# BetaRev1.net
KiCad netlist of a schematic drawn in EAGLE
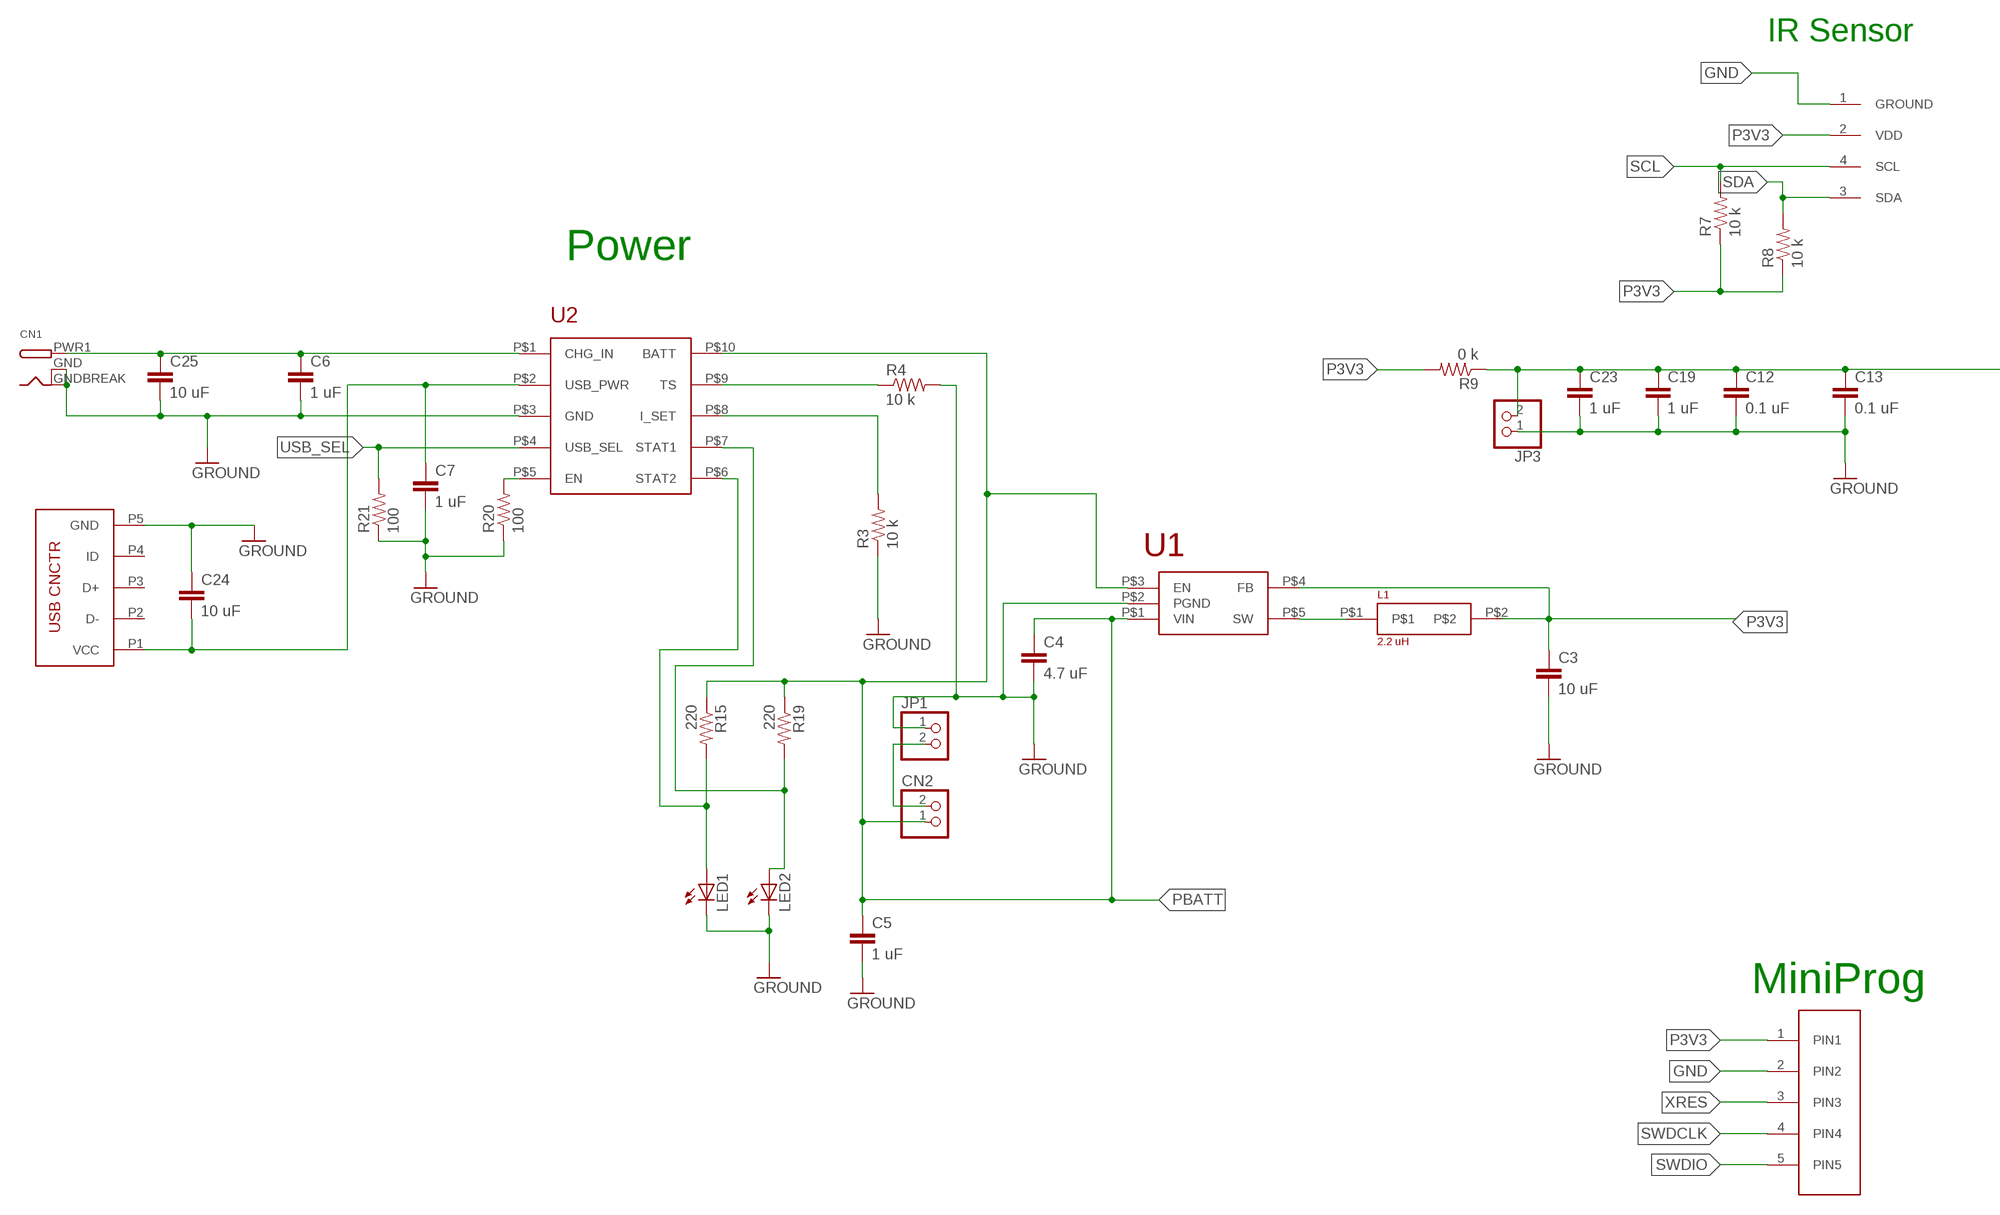
[diagram p0: schematic, sheet 1, part 1 of 2]
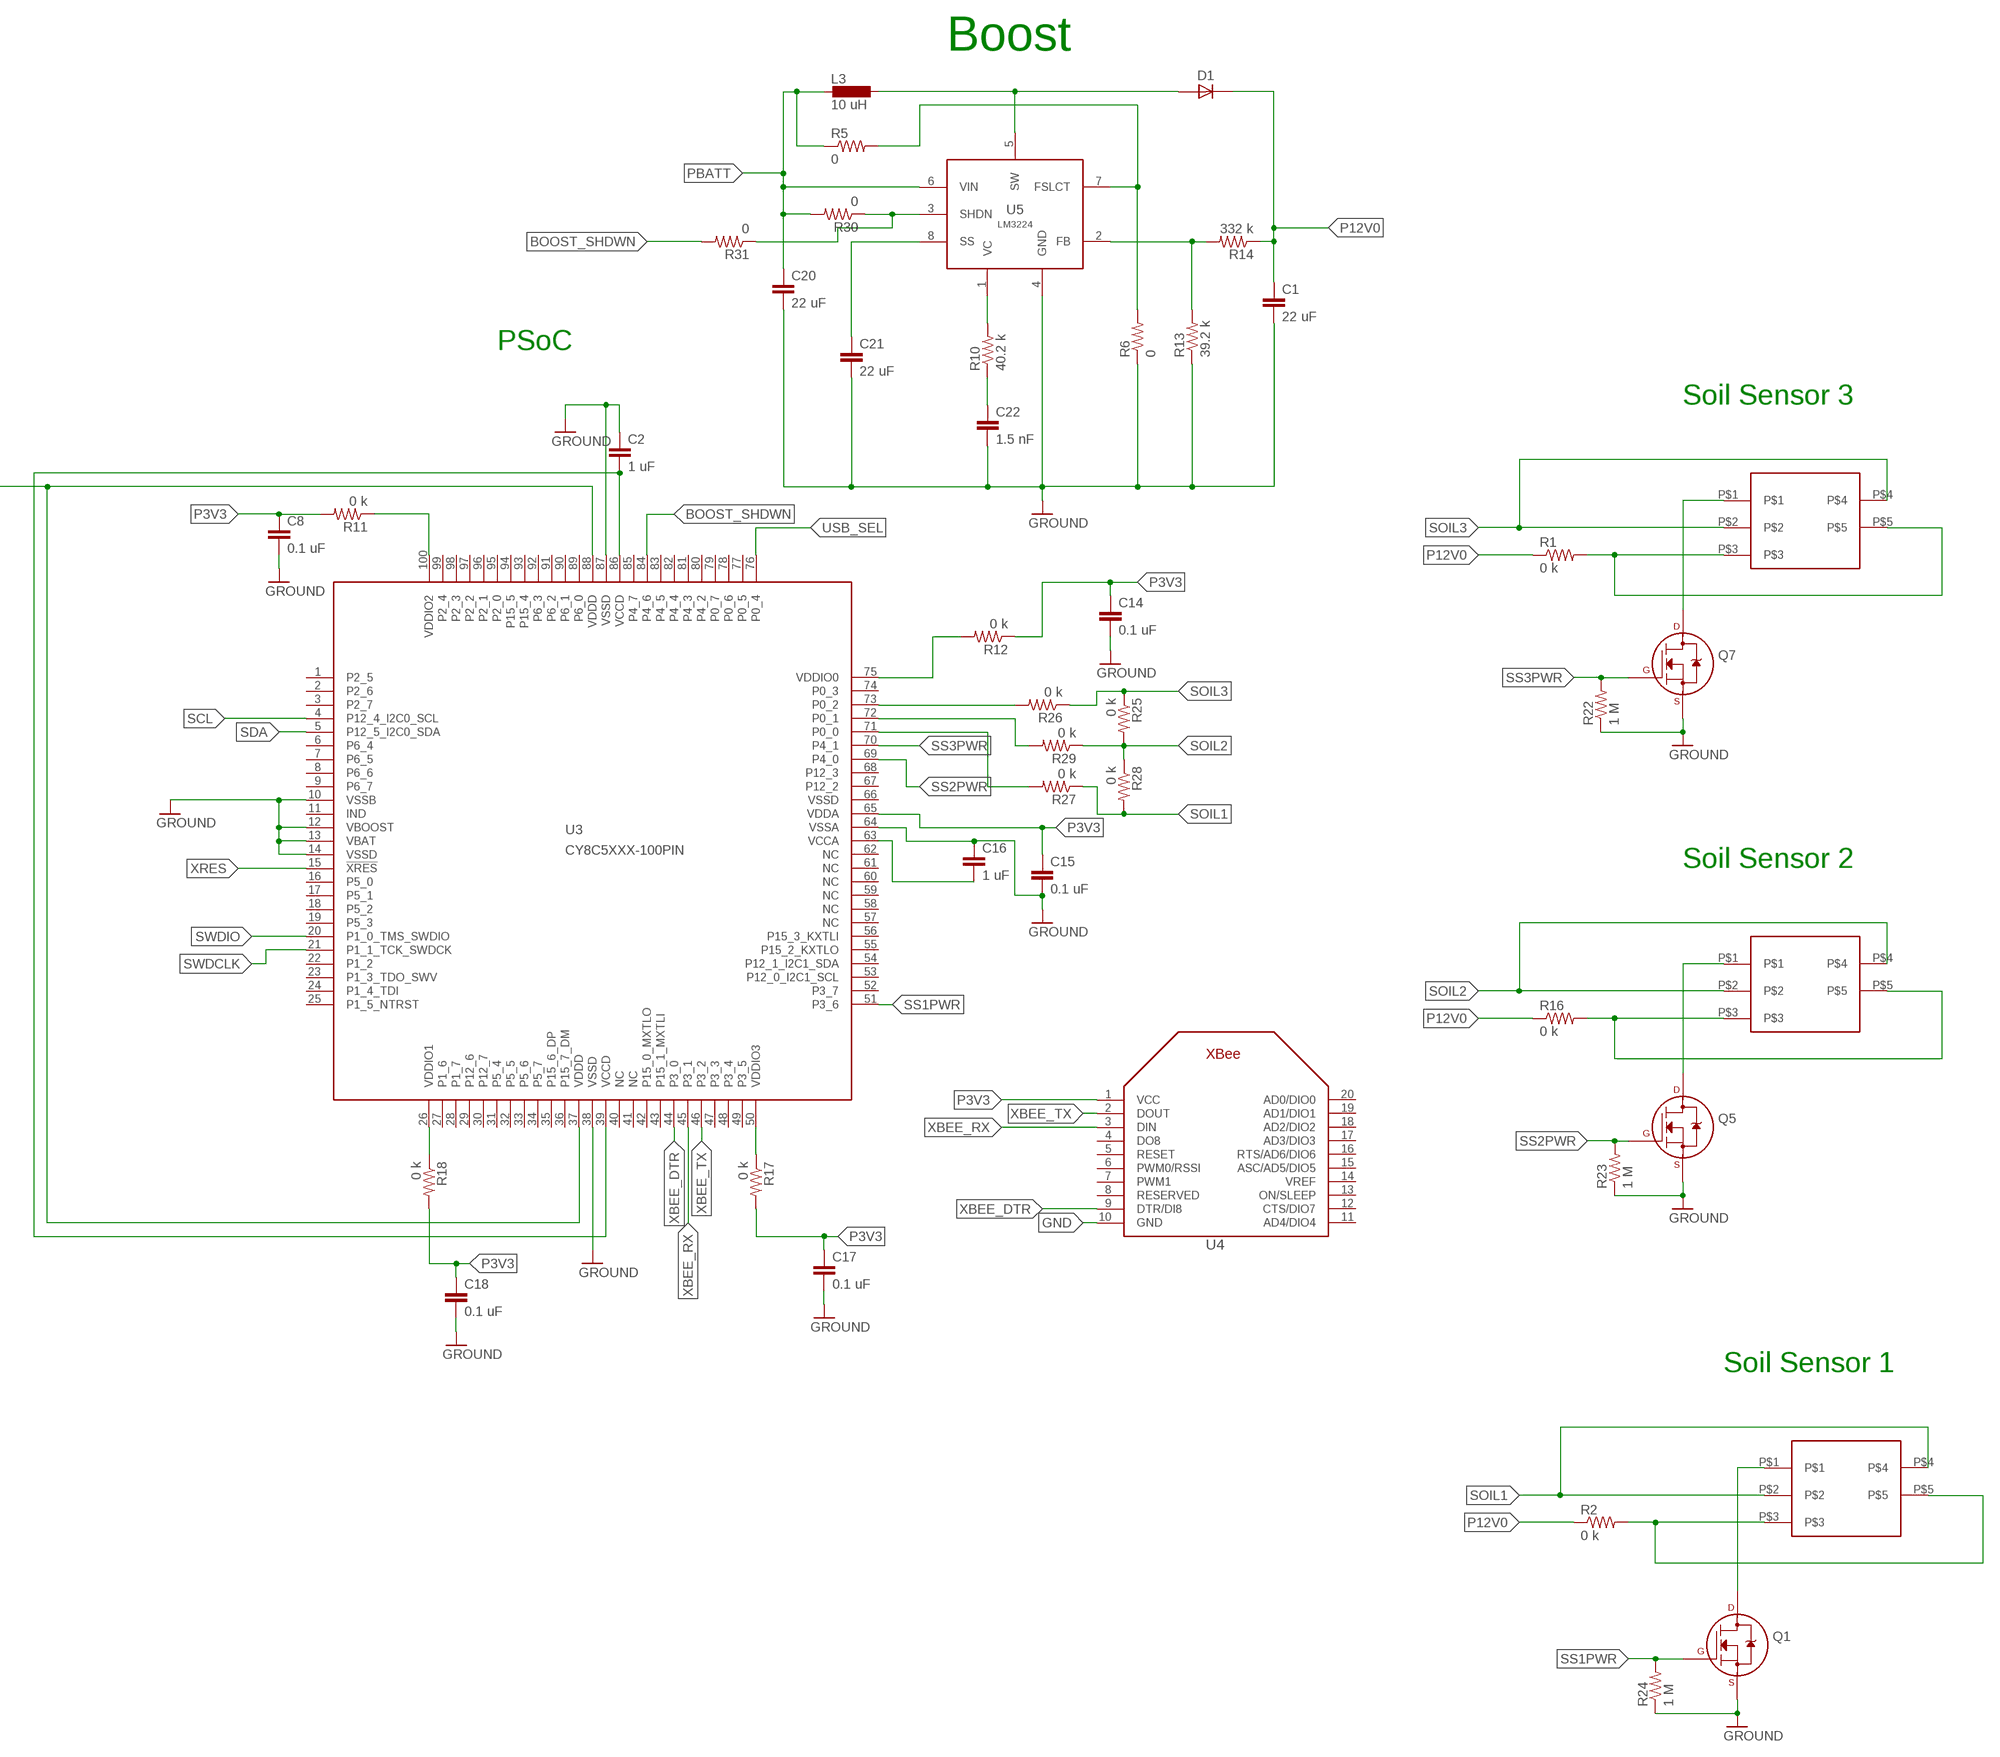
[diagram p1: schematic, sheet 1, part 2 of 2]

(export (version "E")
  (design (tool "Eeschema 10.0.6"))
  (components
    (comp (ref "C1")
      (value "22 uF")
      (footprint "eagle-import:0805")
      (libsource (lib "eagle-import") (part "CAPACITOR0805"))
    )
    (comp (ref "C2")
      (value "1 uF")
      (footprint "eagle-import:0603")
      (libsource (lib "eagle-import") (part "CAPACITOR0603"))
    )
    (comp (ref "C3")
      (value "10 uF")
      (footprint "eagle-import:0603")
      (libsource (lib "eagle-import") (part "CAPACITOR0603"))
    )
    (comp (ref "C4")
      (value "4.7 uF")
      (footprint "eagle-import:0603")
      (libsource (lib "eagle-import") (part "CAPACITOR0603"))
    )
    (comp (ref "C5")
      (value "1 uF")
      (footprint "eagle-import:0603")
      (libsource (lib "eagle-import") (part "CAPACITOR0603"))
    )
    (comp (ref "C6")
      (value "1 uF")
      (footprint "eagle-import:0603")
      (libsource (lib "eagle-import") (part "CAPACITOR0603"))
    )
    (comp (ref "C7")
      (value "1 uF")
      (footprint "eagle-import:0603")
      (libsource (lib "eagle-import") (part "CAPACITOR0603"))
    )
    (comp (ref "C8")
      (value "0.1 uF")
      (footprint "eagle-import:0603")
      (libsource (lib "eagle-import") (part "CAPACITOR0603"))
    )
    (comp (ref "C12")
      (value "0.1 uF")
      (footprint "eagle-import:0603")
      (libsource (lib "eagle-import") (part "CAPACITOR0603"))
    )
    (comp (ref "C13")
      (value "0.1 uF")
      (footprint "eagle-import:0603")
      (libsource (lib "eagle-import") (part "CAPACITOR0603"))
    )
    (comp (ref "C14")
      (value "0.1 uF")
      (footprint "eagle-import:0603")
      (libsource (lib "eagle-import") (part "CAPACITOR0603"))
    )
    (comp (ref "C15")
      (value "0.1 uF")
      (footprint "eagle-import:0603")
      (libsource (lib "eagle-import") (part "CAPACITOR0603"))
    )
    (comp (ref "C16")
      (value "1 uF")
      (footprint "eagle-import:0603")
      (libsource (lib "eagle-import") (part "CAPACITOR0603"))
    )
    (comp (ref "C17")
      (value "0.1 uF")
      (footprint "eagle-import:0603")
      (libsource (lib "eagle-import") (part "CAPACITOR0603"))
    )
    (comp (ref "C18")
      (value "0.1 uF")
      (footprint "eagle-import:0603")
      (libsource (lib "eagle-import") (part "CAPACITOR0603"))
    )
    (comp (ref "C19")
      (value "1 uF")
      (footprint "eagle-import:0603")
      (libsource (lib "eagle-import") (part "CAPACITOR0603"))
    )
    (comp (ref "C20")
      (value "22 uF")
      (footprint "eagle-import:0603")
      (libsource (lib "eagle-import") (part "CAPACITOR0603"))
    )
    (comp (ref "C21")
      (value "22 uF")
      (footprint "eagle-import:0603")
      (libsource (lib "eagle-import") (part "CAPACITOR0603"))
    )
    (comp (ref "C22")
      (value "1.5 nF")
      (footprint "eagle-import:0603")
      (libsource (lib "eagle-import") (part "CAPACITOR0603"))
    )
    (comp (ref "C23")
      (value "1 uF")
      (footprint "eagle-import:0603")
      (libsource (lib "eagle-import") (part "CAPACITOR0603"))
    )
    (comp (ref "C24")
      (value "10 uF")
      (footprint "eagle-import:0603")
      (libsource (lib "eagle-import") (part "CAPACITOR0603"))
    )
    (comp (ref "C25")
      (value "10 uF")
      (footprint "eagle-import:0603")
      (libsource (lib "eagle-import") (part "CAPACITOR0603"))
    )
    (comp (ref "CN1")
      (value "DCBARRELSMT")
      (footprint "eagle-import:DCJACK_2MM_SMT")
      (libsource (lib "eagle-import") (part "DCBARRELSMT"))
    )
    (comp (ref "CN2")
      (value "JST_2PIN-SMT-RA")
      (footprint "eagle-import:JST-PH-2-SMT-RA")
      (libsource (lib "eagle-import") (part "JST_2PIN-SMT-RA"))
    )
    (comp (ref "D1")
      (value "DIODE")
      (footprint "eagle-import:0603-LED")
      (libsource (lib "eagle-import") (part "DIODE"))
    )
    (comp (ref "IRSENSOR")
      (value "TO39")
      (footprint "eagle-import:TO39")
      (libsource (lib "eagle-import") (part "TO39"))
    )
    (comp (ref "JP1")
      (value "PINHD-1X2")
      (footprint "eagle-import:1X02")
      (libsource (lib "eagle-import") (part "PINHD-1X2"))
    )
    (comp (ref "JP3")
      (value "PINHD-1X2")
      (footprint "eagle-import:1X02")
      (libsource (lib "eagle-import") (part "PINHD-1X2"))
    )
    (comp (ref "L1")
      (value "LPO3310")
      (footprint "eagle-import:LPO3310")
      (libsource (lib "eagle-import") (part "LPO3310"))
    )
    (comp (ref "L3")
      (value "10 uH")
      (footprint "eagle-import:DO3316P")
      (libsource (lib "eagle-import") (part "DO3316P"))
    )
    (comp (ref "LED1")
      (value "LEDCHIP-LED0603")
      (footprint "eagle-import:CHIP-LED0603")
      (libsource (lib "eagle-import") (part "LEDCHIP-LED0603"))
    )
    (comp (ref "LED2")
      (value "LEDCHIP-LED0603")
      (footprint "eagle-import:CHIP-LED0603")
      (libsource (lib "eagle-import") (part "LEDCHIP-LED0603"))
    )
    (comp (ref "MINIPROG")
      (value "HEADER-5")
      (footprint "eagle-import:NON-5")
      (libsource (lib "eagle-import") (part "HEADER-5"))
    )
    (comp (ref "Q1")
      (value "2N7000_SOT23")
      (footprint "eagle-import:SOT-23")
      (libsource (lib "eagle-import") (part "2N700_SOT230"))
    )
    (comp (ref "Q5")
      (value "2N7000_SOT23")
      (footprint "eagle-import:SOT-23")
      (libsource (lib "eagle-import") (part "2N700_SOT230"))
    )
    (comp (ref "Q7")
      (value "2N7000_SOT23")
      (footprint "eagle-import:SOT-23")
      (libsource (lib "eagle-import") (part "2N700_SOT230"))
    )
    (comp (ref "R1")
      (value "0 k")
      (footprint "eagle-import:0603")
      (libsource (lib "eagle-import") (part "RESISTOR0603"))
    )
    (comp (ref "R2")
      (value "0 k")
      (footprint "eagle-import:0603")
      (libsource (lib "eagle-import") (part "RESISTOR0603"))
    )
    (comp (ref "R3")
      (value "10 k")
      (footprint "eagle-import:0603")
      (libsource (lib "eagle-import") (part "RESISTOR0603"))
    )
    (comp (ref "R4")
      (value "10 k")
      (footprint "eagle-import:0603")
      (libsource (lib "eagle-import") (part "RESISTOR0603"))
    )
    (comp (ref "R5")
      (value "0")
      (footprint "eagle-import:0603")
      (libsource (lib "eagle-import") (part "RESISTOR0603"))
    )
    (comp (ref "R6")
      (value "0")
      (footprint "eagle-import:0603")
      (libsource (lib "eagle-import") (part "RESISTOR0603"))
    )
    (comp (ref "R7")
      (value "10 k")
      (footprint "eagle-import:0603")
      (libsource (lib "eagle-import") (part "RESISTOR0603"))
    )
    (comp (ref "R8")
      (value "10 k")
      (footprint "eagle-import:0603")
      (libsource (lib "eagle-import") (part "RESISTOR0603"))
    )
    (comp (ref "R9")
      (value "0 k")
      (footprint "eagle-import:0603")
      (libsource (lib "eagle-import") (part "RESISTOR0603"))
    )
    (comp (ref "R10")
      (value "40.2 k")
      (footprint "eagle-import:0603")
      (libsource (lib "eagle-import") (part "RESISTOR0603"))
    )
    (comp (ref "R11")
      (value "0 k")
      (footprint "eagle-import:0603")
      (libsource (lib "eagle-import") (part "RESISTOR0603"))
    )
    (comp (ref "R12")
      (value "0 k")
      (footprint "eagle-import:0603")
      (libsource (lib "eagle-import") (part "RESISTOR0603"))
    )
    (comp (ref "R13")
      (value "39.2 k")
      (footprint "eagle-import:0603")
      (libsource (lib "eagle-import") (part "RESISTOR0603"))
    )
    (comp (ref "R14")
      (value "332 k")
      (footprint "eagle-import:0603")
      (libsource (lib "eagle-import") (part "RESISTOR0603"))
    )
    (comp (ref "R15")
      (value "220")
      (footprint "eagle-import:0603")
      (libsource (lib "eagle-import") (part "RESISTOR0603"))
    )
    (comp (ref "R16")
      (value "0 k")
      (footprint "eagle-import:0603")
      (libsource (lib "eagle-import") (part "RESISTOR0603"))
    )
    (comp (ref "R17")
      (value "0 k")
      (footprint "eagle-import:0603")
      (libsource (lib "eagle-import") (part "RESISTOR0603"))
    )
    (comp (ref "R18")
      (value "0 k")
      (footprint "eagle-import:0603")
      (libsource (lib "eagle-import") (part "RESISTOR0603"))
    )
    (comp (ref "R19")
      (value "220")
      (footprint "eagle-import:0603")
      (libsource (lib "eagle-import") (part "RESISTOR0603"))
    )
    (comp (ref "R20")
      (value "100")
      (footprint "eagle-import:0603")
      (libsource (lib "eagle-import") (part "RESISTOR0603"))
    )
    (comp (ref "R21")
      (value "100")
      (footprint "eagle-import:0603")
      (libsource (lib "eagle-import") (part "RESISTOR0603"))
    )
    (comp (ref "R22")
      (value "1 M")
      (footprint "eagle-import:0603")
      (libsource (lib "eagle-import") (part "RESISTOR0603"))
    )
    (comp (ref "R23")
      (value "1 M")
      (footprint "eagle-import:0603")
      (libsource (lib "eagle-import") (part "RESISTOR0603"))
    )
    (comp (ref "R24")
      (value "1 M")
      (footprint "eagle-import:0603")
      (libsource (lib "eagle-import") (part "RESISTOR0603"))
    )
    (comp (ref "R25")
      (value "0 k")
      (footprint "eagle-import:0603")
      (libsource (lib "eagle-import") (part "RESISTOR0603"))
    )
    (comp (ref "R26")
      (value "0 k")
      (footprint "eagle-import:0603")
      (libsource (lib "eagle-import") (part "RESISTOR0603"))
    )
    (comp (ref "R27")
      (value "0 k")
      (footprint "eagle-import:0603")
      (libsource (lib "eagle-import") (part "RESISTOR0603"))
    )
    (comp (ref "R28")
      (value "0 k")
      (footprint "eagle-import:0603")
      (libsource (lib "eagle-import") (part "RESISTOR0603"))
    )
    (comp (ref "R29")
      (value "0 k")
      (footprint "eagle-import:0603")
      (libsource (lib "eagle-import") (part "RESISTOR0603"))
    )
    (comp (ref "R30")
      (value "0")
      (footprint "eagle-import:0603")
      (libsource (lib "eagle-import") (part "RESISTOR0603"))
    )
    (comp (ref "R31")
      (value "0")
      (footprint "eagle-import:0603")
      (libsource (lib "eagle-import") (part "RESISTOR0603"))
    )
    (comp (ref "U$1")
      (value "FCI10118192-0001LF")
      (footprint "eagle-import:FCI10118192-0001LF")
      (libsource (lib "eagle-import") (part "FCI10118192-0001LF"))
    )
    (comp (ref "U$2")
      (value "AUDIOJACK")
      (footprint "eagle-import:AUDIOJACK")
      (libsource (lib "eagle-import") (part "AUDIOJACK"))
    )
    (comp (ref "U$3")
      (value "AUDIOJACK")
      (footprint "eagle-import:AUDIOJACK")
      (libsource (lib "eagle-import") (part "AUDIOJACK"))
    )
    (comp (ref "U$4")
      (value "AUDIOJACK")
      (footprint "eagle-import:AUDIOJACK")
      (libsource (lib "eagle-import") (part "AUDIOJACK"))
    )
    (comp (ref "U1")
      (value "LM3671-407564")
      (footprint "eagle-import:LM3671-407564")
      (libsource (lib "eagle-import") (part "LM3671-407564"))
    )
    (comp (ref "U2")
      (value "LM3658")
      (footprint "eagle-import:LM3658")
      (libsource (lib "eagle-import") (part "LM3658"))
    )
    (comp (ref "U3")
      (value "CY8C5XXX-100PIN")
      (footprint "eagle-import:TQFP-14X14-100")
      (fields (field (name "MPN") "CY8C5588AXI-060"))
      (libsource (lib "eagle-import") (part "CY8C5XXX-100PIN"))
    )
    (comp (ref "U4")
      (value "XBEE")
      (footprint "eagle-import:XBEE")
      (libsource (lib "eagle-import") (part "XBEE"))
    )
    (comp (ref "U5")
      (value "LM3224")
      (footprint "eagle-import:MSOP-8")
      (libsource (lib "eagle-import") (part "LM3224"))
    )
  )
  (nets
    (net (code "1") (name "BOOST_SHDWN") (class "Default")
      (node (ref "R31") (pin "2") (pinfunction "2_2") (pintype "passive"))
      (node (ref "U3") (pin "84") (pinfunction "P4_6_84") (pintype "passive"))
    )
    (net (code "2") (name "GND") (class "Default")
      (node (ref "C1") (pin "2") (pinfunction "2_2") (pintype "passive"))
      (node (ref "C12") (pin "2") (pinfunction "2_2") (pintype "passive"))
      (node (ref "C13") (pin "2") (pinfunction "2_2") (pintype "passive"))
      (node (ref "C14") (pin "2") (pinfunction "2_2") (pintype "passive"))
      (node (ref "C15") (pin "2") (pinfunction "2_2") (pintype "passive"))
      (node (ref "C16") (pin "1") (pinfunction "1_1") (pintype "passive"))
      (node (ref "C17") (pin "2") (pinfunction "2_2") (pintype "passive"))
      (node (ref "C18") (pin "2") (pinfunction "2_2") (pintype "passive"))
      (node (ref "C19") (pin "2") (pinfunction "2_2") (pintype "passive"))
      (node (ref "C2") (pin "1") (pinfunction "1_1") (pintype "passive"))
      (node (ref "C20") (pin "2") (pinfunction "2_2") (pintype "passive"))
      (node (ref "C21") (pin "2") (pinfunction "2_2") (pintype "passive"))
      (node (ref "C22") (pin "2") (pinfunction "2_2") (pintype "passive"))
      (node (ref "C23") (pin "2") (pinfunction "2_2") (pintype "passive"))
      (node (ref "C24") (pin "1") (pinfunction "1_1") (pintype "passive"))
      (node (ref "C25") (pin "2") (pinfunction "2_2") (pintype "passive"))
      (node (ref "C3") (pin "2") (pinfunction "2_2") (pintype "passive"))
      (node (ref "C4") (pin "2") (pinfunction "2_2") (pintype "passive"))
      (node (ref "C5") (pin "2") (pinfunction "2_2") (pintype "passive"))
      (node (ref "C6") (pin "2") (pinfunction "2_2") (pintype "passive"))
      (node (ref "C7") (pin "2") (pinfunction "2_2") (pintype "passive"))
      (node (ref "C8") (pin "2") (pinfunction "2_2") (pintype "passive"))
      (node (ref "CN1") (pin "GND") (pinfunction "GNDBREAK_GND") (pintype "power_in"))
      (node (ref "CN1") (pin "GNDBREAK") (pinfunction "GND_GNDBREAK") (pintype "power_in"))
      (node (ref "IRSENSOR") (pin "1") (pinfunction "GROUND_1") (pintype "bidirectional"))
      (node (ref "JP1") (pin "1") (pinfunction "1_1") (pintype "passive"))
      (node (ref "JP3") (pin "1") (pinfunction "1_1") (pintype "passive"))
      (node (ref "LED1") (pin "C") (pinfunction "C_C") (pintype "passive"))
      (node (ref "LED2") (pin "C") (pinfunction "C_C") (pintype "passive"))
      (node (ref "MINIPROG") (pin "2") (pinfunction "PIN2_2") (pintype "bidirectional"))
      (node (ref "Q1") (pin "2") (pinfunction "S_2") (pintype "bidirectional"))
      (node (ref "Q5") (pin "2") (pinfunction "S_2") (pintype "bidirectional"))
      (node (ref "Q7") (pin "2") (pinfunction "S_2") (pintype "bidirectional"))
      (node (ref "R13") (pin "1") (pinfunction "1_1") (pintype "passive"))
      (node (ref "R20") (pin "1") (pinfunction "1_1") (pintype "passive"))
      (node (ref "R21") (pin "1") (pinfunction "1_1") (pintype "passive"))
      (node (ref "R22") (pin "1") (pinfunction "1_1") (pintype "passive"))
      (node (ref "R23") (pin "1") (pinfunction "1_1") (pintype "passive"))
      (node (ref "R24") (pin "1") (pinfunction "1_1") (pintype "passive"))
      (node (ref "R3") (pin "1") (pinfunction "1_1") (pintype "passive"))
      (node (ref "R4") (pin "2") (pinfunction "2_2") (pintype "passive"))
      (node (ref "R6") (pin "1") (pinfunction "1_1") (pintype "passive"))
      (node (ref "U$1") (pin "P5") (pinfunction "GND_P5") (pintype "power_in"))
      (node (ref "U1") (pin "P$2") (pinfunction "PGND_P$2") (pintype "passive"))
      (node (ref "U2") (pin "P$3") (pinfunction "GND_P$3") (pintype "power_in"))
      (node (ref "U3") (pin "10") (pinfunction "VSSB_10") (pintype "passive"))
      (node (ref "U3") (pin "12") (pinfunction "VBOOST_12") (pintype "passive"))
      (node (ref "U3") (pin "13") (pinfunction "VBAT_13") (pintype "passive"))
      (node (ref "U3") (pin "14") (pinfunction "VSSD_14") (pintype "passive"))
      (node (ref "U3") (pin "38") (pinfunction "VSSD_38") (pintype "passive"))
      (node (ref "U3") (pin "64") (pinfunction "VSSA_64") (pintype "passive"))
      (node (ref "U3") (pin "87") (pinfunction "VSSD_87") (pintype "passive"))
      (node (ref "U4") (pin "10") (pinfunction "GND_10") (pintype "power_in"))
      (node (ref "U5") (pin "4") (pinfunction "GND_4") (pintype "bidirectional"))
    )
    (net (code "3") (name "Net-(C2-Pad2)") (class "Default")
      (node (ref "C2") (pin "2") (pinfunction "2_2") (pintype "passive"))
      (node (ref "U3") (pin "39") (pinfunction "VCCD_39") (pintype "passive"))
      (node (ref "U3") (pin "86") (pinfunction "VCCD_86") (pintype "passive"))
    )
    (net (code "4") (name "Net-(C12-Pad1)") (class "Default")
      (node (ref "C12") (pin "1") (pinfunction "1_1") (pintype "passive"))
      (node (ref "C13") (pin "1") (pinfunction "1_1") (pintype "passive"))
      (node (ref "C19") (pin "1") (pinfunction "1_1") (pintype "passive"))
      (node (ref "C23") (pin "1") (pinfunction "1_1") (pintype "passive"))
      (node (ref "JP3") (pin "2") (pinfunction "2_2") (pintype "passive"))
      (node (ref "R9") (pin "1") (pinfunction "1_1") (pintype "passive"))
      (node (ref "U3") (pin "37") (pinfunction "VDDD_37") (pintype "passive"))
      (node (ref "U3") (pin "88") (pinfunction "VDDD_88") (pintype "passive"))
    )
    (net (code "5") (name "Net-(C22-Pad1)") (class "Default")
      (node (ref "C22") (pin "1") (pinfunction "1_1") (pintype "passive"))
      (node (ref "R10") (pin "1") (pinfunction "1_1") (pintype "passive"))
    )
    (net (code "6") (name "Net-(CN1-PWR)") (class "Default")
      (node (ref "C25") (pin "1") (pinfunction "1_1") (pintype "passive"))
      (node (ref "C6") (pin "1") (pinfunction "1_1") (pintype "passive"))
      (node (ref "CN1") (pin "PWR1") (pinfunction "PWR_PWR1") (pintype "power_in"))
      (node (ref "U2") (pin "P$1") (pinfunction "CHG_IN_P$1") (pintype "power_in"))
    )
    (net (code "7") (name "Net-(CN2-1)") (class "Default")
      (node (ref "CN2") (pin "2") (pinfunction "1_2") (pintype "passive"))
      (node (ref "JP1") (pin "2") (pinfunction "2_2") (pintype "passive"))
    )
    (net (code "8") (name "Net-(Q1-D)") (class "Default")
      (node (ref "Q1") (pin "3") (pinfunction "D_3") (pintype "bidirectional"))
      (node (ref "U$4") (pin "P$1") (pinfunction "P$1_P$1") (pintype "output"))
    )
    (net (code "9") (name "Net-(Q5-D)") (class "Default")
      (node (ref "Q5") (pin "3") (pinfunction "D_3") (pintype "bidirectional"))
      (node (ref "U$2") (pin "P$1") (pinfunction "P$1_P$1") (pintype "output"))
    )
    (net (code "10") (name "Net-(Q7-D)") (class "Default")
      (node (ref "Q7") (pin "3") (pinfunction "D_3") (pintype "bidirectional"))
      (node (ref "U$3") (pin "P$1") (pinfunction "P$1_P$1") (pintype "output"))
    )
    (net (code "11") (name "Net-(R1-Pad2)") (class "Default")
      (node (ref "R1") (pin "2") (pinfunction "2_2") (pintype "passive"))
      (node (ref "U$3") (pin "P$3") (pinfunction "P$3_P$3") (pintype "output"))
      (node (ref "U$3") (pin "P$5") (pinfunction "P$5_P$5") (pintype "output"))
    )
    (net (code "12") (name "Net-(R2-Pad2)") (class "Default")
      (node (ref "R2") (pin "2") (pinfunction "2_2") (pintype "passive"))
      (node (ref "U$4") (pin "P$3") (pinfunction "P$3_P$3") (pintype "output"))
      (node (ref "U$4") (pin "P$5") (pinfunction "P$5_P$5") (pintype "output"))
    )
    (net (code "13") (name "Net-(R16-Pad2)") (class "Default")
      (node (ref "R16") (pin "2") (pinfunction "2_2") (pintype "passive"))
      (node (ref "U$2") (pin "P$3") (pinfunction "P$3_P$3") (pintype "output"))
      (node (ref "U$2") (pin "P$5") (pinfunction "P$5_P$5") (pintype "output"))
    )
    (net (code "14") (name "Net-(U$1-VCC)") (class "Default")
      (node (ref "C24") (pin "2") (pinfunction "2_2") (pintype "passive"))
      (node (ref "C7") (pin "1") (pinfunction "1_1") (pintype "passive"))
      (node (ref "U$1") (pin "P1") (pinfunction "VCC_P1") (pintype "power_in"))
      (node (ref "U2") (pin "P$2") (pinfunction "USB_PWR_P$2") (pintype "power_in"))
    )
    (net (code "15") (name "Net-(U1-SW)") (class "Default")
      (node (ref "L1") (pin "P$1") (pinfunction "P$1_P$1") (pintype "passive"))
      (node (ref "U1") (pin "P$5") (pinfunction "SW_P$5") (pintype "bidirectional"))
    )
    (net (code "16") (name "Net-(U2-EN)") (class "Default")
      (node (ref "R20") (pin "2") (pinfunction "2_2") (pintype "passive"))
      (node (ref "U2") (pin "P$5") (pinfunction "EN_P$5") (pintype "input"))
    )
    (net (code "17") (name "Net-(U2-I_SET)") (class "Default")
      (node (ref "R3") (pin "2") (pinfunction "2_2") (pintype "passive"))
      (node (ref "U2") (pin "P$8") (pinfunction "I_SET_P$8") (pintype "bidirectional"))
    )
    (net (code "18") (name "Net-(U2-STAT1)") (class "Default")
      (node (ref "LED2") (pin "A") (pinfunction "A_A") (pintype "passive"))
      (node (ref "R19") (pin "2") (pinfunction "2_2") (pintype "passive"))
      (node (ref "U2") (pin "P$7") (pinfunction "STAT1_P$7") (pintype "output"))
    )
    (net (code "19") (name "Net-(U2-STAT2)") (class "Default")
      (node (ref "LED1") (pin "A") (pinfunction "A_A") (pintype "passive"))
      (node (ref "R15") (pin "2") (pinfunction "2_2") (pintype "passive"))
      (node (ref "U2") (pin "P$6") (pinfunction "STAT2_P$6") (pintype "output"))
    )
    (net (code "20") (name "Net-(U2-TS)") (class "Default")
      (node (ref "R4") (pin "1") (pinfunction "1_1") (pintype "passive"))
      (node (ref "U2") (pin "P$9") (pinfunction "TS_P$9") (pintype "bidirectional"))
    )
    (net (code "21") (name "Net-(U3-P0_0)") (class "Default")
      (node (ref "R27") (pin "2") (pinfunction "2_2") (pintype "passive"))
      (node (ref "U3") (pin "71") (pinfunction "P0_0_71") (pintype "passive"))
    )
    (net (code "22") (name "Net-(U3-P0_1)") (class "Default")
      (node (ref "R29") (pin "2") (pinfunction "2_2") (pintype "passive"))
      (node (ref "U3") (pin "72") (pinfunction "P0_1_72") (pintype "passive"))
    )
    (net (code "23") (name "Net-(U3-P0_2)") (class "Default")
      (node (ref "R26") (pin "2") (pinfunction "2_2") (pintype "passive"))
      (node (ref "U3") (pin "73") (pinfunction "P0_2_73") (pintype "passive"))
    )
    (net (code "24") (name "Net-(U3-VCCA)") (class "Default")
      (node (ref "C16") (pin "2") (pinfunction "2_2") (pintype "passive"))
      (node (ref "U3") (pin "63") (pinfunction "VCCA_63") (pintype "passive"))
    )
    (net (code "25") (name "Net-(U3-VDDIO0)") (class "Default")
      (node (ref "R12") (pin "2") (pinfunction "2_2") (pintype "passive"))
      (node (ref "U3") (pin "75") (pinfunction "VDDIO0_75") (pintype "passive"))
    )
    (net (code "26") (name "Net-(U3-VDDIO1)") (class "Default")
      (node (ref "R18") (pin "1") (pinfunction "1_1") (pintype "passive"))
      (node (ref "U3") (pin "26") (pinfunction "VDDIO1_26") (pintype "passive"))
    )
    (net (code "27") (name "Net-(U3-VDDIO2)") (class "Default")
      (node (ref "R11") (pin "1") (pinfunction "1_1") (pintype "passive"))
      (node (ref "U3") (pin "100") (pinfunction "VDDIO2_100") (pintype "passive"))
    )
    (net (code "28") (name "Net-(U3-VDDIO3)") (class "Default")
      (node (ref "R17") (pin "1") (pinfunction "1_1") (pintype "passive"))
      (node (ref "U3") (pin "50") (pinfunction "VDDIO3_50") (pintype "passive"))
    )
    (net (code "29") (name "Net-(U5-FB)") (class "Default")
      (node (ref "R13") (pin "2") (pinfunction "2_2") (pintype "passive"))
      (node (ref "R14") (pin "2") (pinfunction "2_2") (pintype "passive"))
      (node (ref "U5") (pin "2") (pinfunction "FB_2") (pintype "bidirectional"))
    )
    (net (code "30") (name "Net-(U5-FSLCT)") (class "Default")
      (node (ref "R5") (pin "2") (pinfunction "2_2") (pintype "passive"))
      (node (ref "R6") (pin "2") (pinfunction "2_2") (pintype "passive"))
      (node (ref "U5") (pin "7") (pinfunction "FSLCT_7") (pintype "bidirectional"))
    )
    (net (code "31") (name "Net-(U5-SHDN)") (class "Default")
      (node (ref "R30") (pin "1") (pinfunction "1_1") (pintype "passive"))
      (node (ref "R31") (pin "1") (pinfunction "1_1") (pintype "passive"))
      (node (ref "U5") (pin "3") (pinfunction "SHDN_3") (pintype "bidirectional"))
    )
    (net (code "32") (name "Net-(U5-SS)") (class "Default")
      (node (ref "C21") (pin "1") (pinfunction "1_1") (pintype "passive"))
      (node (ref "U5") (pin "8") (pinfunction "SS_8") (pintype "bidirectional"))
    )
    (net (code "33") (name "Net-(U5-SW)") (class "Default")
      (node (ref "D1") (pin "A") (pinfunction "A_A") (pintype "passive"))
      (node (ref "L3") (pin "2") (pinfunction "2_2") (pintype "passive"))
      (node (ref "U5") (pin "5") (pinfunction "SW_5") (pintype "bidirectional"))
    )
    (net (code "34") (name "Net-(U5-VC)") (class "Default")
      (node (ref "R10") (pin "2") (pinfunction "2_2") (pintype "passive"))
      (node (ref "U5") (pin "1") (pinfunction "VC_1") (pintype "bidirectional"))
    )
    (net (code "35") (name "P3V3") (class "Default")
      (node (ref "C14") (pin "1") (pinfunction "1_1") (pintype "passive"))
      (node (ref "C15") (pin "1") (pinfunction "1_1") (pintype "passive"))
      (node (ref "C17") (pin "1") (pinfunction "1_1") (pintype "passive"))
      (node (ref "C18") (pin "1") (pinfunction "1_1") (pintype "passive"))
      (node (ref "C3") (pin "1") (pinfunction "1_1") (pintype "passive"))
      (node (ref "C8") (pin "1") (pinfunction "1_1") (pintype "passive"))
      (node (ref "IRSENSOR") (pin "2") (pinfunction "VDD_2") (pintype "bidirectional"))
      (node (ref "L1") (pin "P$2") (pinfunction "P$2_P$2") (pintype "tri_state"))
      (node (ref "MINIPROG") (pin "1") (pinfunction "PIN1_1") (pintype "bidirectional"))
      (node (ref "R11") (pin "2") (pinfunction "2_2") (pintype "passive"))
      (node (ref "R12") (pin "1") (pinfunction "1_1") (pintype "passive"))
      (node (ref "R17") (pin "2") (pinfunction "2_2") (pintype "passive"))
      (node (ref "R18") (pin "2") (pinfunction "2_2") (pintype "passive"))
      (node (ref "R7") (pin "1") (pinfunction "1_1") (pintype "passive"))
      (node (ref "R8") (pin "1") (pinfunction "1_1") (pintype "passive"))
      (node (ref "R9") (pin "2") (pinfunction "2_2") (pintype "passive"))
      (node (ref "U1") (pin "P$4") (pinfunction "FB_P$4") (pintype "bidirectional"))
      (node (ref "U3") (pin "65") (pinfunction "VDDA_65") (pintype "passive"))
      (node (ref "U4") (pin "1") (pinfunction "VCC_1") (pintype "power_in"))
    )
    (net (code "36") (name "P12V0") (class "Default")
      (node (ref "C1") (pin "1") (pinfunction "1_1") (pintype "passive"))
      (node (ref "D1") (pin "C") (pinfunction "C_C") (pintype "passive"))
      (node (ref "R1") (pin "1") (pinfunction "1_1") (pintype "passive"))
      (node (ref "R14") (pin "1") (pinfunction "1_1") (pintype "passive"))
      (node (ref "R16") (pin "1") (pinfunction "1_1") (pintype "passive"))
      (node (ref "R2") (pin "1") (pinfunction "1_1") (pintype "passive"))
    )
    (net (code "37") (name "PBATT") (class "Default")
      (node (ref "C20") (pin "1") (pinfunction "1_1") (pintype "passive"))
      (node (ref "C4") (pin "1") (pinfunction "1_1") (pintype "passive"))
      (node (ref "C5") (pin "1") (pinfunction "1_1") (pintype "passive"))
      (node (ref "CN2") (pin "1") (pinfunction "2_1") (pintype "passive"))
      (node (ref "L3") (pin "1") (pinfunction "1_1") (pintype "passive"))
      (node (ref "R15") (pin "1") (pinfunction "1_1") (pintype "passive"))
      (node (ref "R19") (pin "1") (pinfunction "1_1") (pintype "passive"))
      (node (ref "R30") (pin "2") (pinfunction "2_2") (pintype "passive"))
      (node (ref "R5") (pin "1") (pinfunction "1_1") (pintype "passive"))
      (node (ref "U1") (pin "P$1") (pinfunction "VIN_P$1") (pintype "power_in"))
      (node (ref "U1") (pin "P$3") (pinfunction "EN_P$3") (pintype "bidirectional"))
      (node (ref "U2") (pin "P$10") (pinfunction "BATT_P$10") (pintype "power_in"))
      (node (ref "U5") (pin "6") (pinfunction "VIN_6") (pintype "bidirectional"))
    )
    (net (code "38") (name "SCL") (class "Default")
      (node (ref "IRSENSOR") (pin "4") (pinfunction "SCL_4") (pintype "bidirectional"))
      (node (ref "R7") (pin "2") (pinfunction "2_2") (pintype "passive"))
      (node (ref "U3") (pin "4") (pinfunction "P12_4_I2C0_SCL_4") (pintype "passive"))
    )
    (net (code "39") (name "SDA") (class "Default")
      (node (ref "IRSENSOR") (pin "3") (pinfunction "SDA_3") (pintype "bidirectional"))
      (node (ref "R8") (pin "2") (pinfunction "2_2") (pintype "passive"))
      (node (ref "U3") (pin "5") (pinfunction "P12_5_I2C0_SDA_5") (pintype "passive"))
    )
    (net (code "40") (name "SOIL1") (class "Default")
      (node (ref "R27") (pin "1") (pinfunction "1_1") (pintype "passive"))
      (node (ref "R28") (pin "2") (pinfunction "2_2") (pintype "passive"))
      (node (ref "U$4") (pin "P$2") (pinfunction "P$2_P$2") (pintype "output"))
      (node (ref "U$4") (pin "P$4") (pinfunction "P$4_P$4") (pintype "output"))
    )
    (net (code "41") (name "SOIL2") (class "Default")
      (node (ref "R25") (pin "2") (pinfunction "2_2") (pintype "passive"))
      (node (ref "R28") (pin "1") (pinfunction "1_1") (pintype "passive"))
      (node (ref "R29") (pin "1") (pinfunction "1_1") (pintype "passive"))
      (node (ref "U$2") (pin "P$2") (pinfunction "P$2_P$2") (pintype "output"))
      (node (ref "U$2") (pin "P$4") (pinfunction "P$4_P$4") (pintype "output"))
    )
    (net (code "42") (name "SOIL3") (class "Default")
      (node (ref "R25") (pin "1") (pinfunction "1_1") (pintype "passive"))
      (node (ref "R26") (pin "1") (pinfunction "1_1") (pintype "passive"))
      (node (ref "U$3") (pin "P$2") (pinfunction "P$2_P$2") (pintype "output"))
      (node (ref "U$3") (pin "P$4") (pinfunction "P$4_P$4") (pintype "output"))
    )
    (net (code "43") (name "SS1PWR") (class "Default")
      (node (ref "Q1") (pin "1") (pinfunction "G_1") (pintype "tri_state"))
      (node (ref "R24") (pin "2") (pinfunction "2_2") (pintype "passive"))
      (node (ref "U3") (pin "51") (pinfunction "P3_6_51") (pintype "passive"))
    )
    (net (code "44") (name "SS2PWR") (class "Default")
      (node (ref "Q5") (pin "1") (pinfunction "G_1") (pintype "tri_state"))
      (node (ref "R23") (pin "2") (pinfunction "2_2") (pintype "passive"))
      (node (ref "U3") (pin "69") (pinfunction "P4_0_69") (pintype "passive"))
    )
    (net (code "45") (name "SS3PWR") (class "Default")
      (node (ref "Q7") (pin "1") (pinfunction "G_1") (pintype "tri_state"))
      (node (ref "R22") (pin "2") (pinfunction "2_2") (pintype "passive"))
      (node (ref "U3") (pin "70") (pinfunction "P4_1_70") (pintype "passive"))
    )
    (net (code "46") (name "SWDCLK") (class "Default")
      (node (ref "MINIPROG") (pin "4") (pinfunction "PIN4_4") (pintype "bidirectional"))
      (node (ref "U3") (pin "21") (pinfunction "P1_1_TCK_SWDCK_21") (pintype "passive"))
    )
    (net (code "47") (name "SWDIO") (class "Default")
      (node (ref "MINIPROG") (pin "5") (pinfunction "PIN5_5") (pintype "bidirectional"))
      (node (ref "U3") (pin "20") (pinfunction "P1_0_TMS_SWDIO_20") (pintype "passive"))
    )
    (net (code "48") (name "USB_SEL") (class "Default")
      (node (ref "R21") (pin "2") (pinfunction "2_2") (pintype "passive"))
      (node (ref "U2") (pin "P$4") (pinfunction "USB_SEL_P$4") (pintype "input"))
      (node (ref "U3") (pin "76") (pinfunction "P0_4_76") (pintype "passive"))
    )
    (net (code "49") (name "XBEE_DTR") (class "Default")
      (node (ref "U3") (pin "44") (pinfunction "P3_0_44") (pintype "passive"))
      (node (ref "U4") (pin "9") (pinfunction "DTR/DI8_9") (pintype "input"))
    )
    (net (code "50") (name "XBEE_RX") (class "Default")
      (node (ref "U3") (pin "45") (pinfunction "P3_1_45") (pintype "passive"))
      (node (ref "U4") (pin "3") (pinfunction "DIN_3") (pintype "input"))
    )
    (net (code "51") (name "XBEE_TX") (class "Default")
      (node (ref "U3") (pin "46") (pinfunction "P3_2_46") (pintype "passive"))
      (node (ref "U4") (pin "2") (pinfunction "DOUT_2") (pintype "output"))
    )
    (net (code "52") (name "XRES") (class "Default")
      (node (ref "MINIPROG") (pin "3") (pinfunction "PIN3_3") (pintype "bidirectional"))
      (node (ref "U3") (pin "15") (pinfunction "~{XRES}_15") (pintype "passive"))
    )
    (net (code "53") (name "unconnected-(U$1-D+-PadP3)") (class "Default")
      (node (ref "U$1") (pin "P3") (pinfunction "D+_P3") (pintype "bidirectional"))
    )
    (net (code "54") (name "unconnected-(U$1-D--PadP2)") (class "Default")
      (node (ref "U$1") (pin "P2") (pinfunction "D-_P2") (pintype "bidirectional"))
    )
    (net (code "55") (name "unconnected-(U$1-ID-PadP4)") (class "Default")
      (node (ref "U$1") (pin "P4") (pinfunction "ID_P4") (pintype "bidirectional"))
    )
    (net (code "56") (name "unconnected-(U3-IND-Pad11)") (class "Default")
      (node (ref "U3") (pin "11") (pinfunction "IND_11") (pintype "passive"))
    )
    (net (code "57") (name "unconnected-(U3-NC-Pad40)") (class "Default")
      (node (ref "U3") (pin "40") (pinfunction "NC_40") (pintype "passive"))
    )
    (net (code "58") (name "unconnected-(U3-NC-Pad41)") (class "Default")
      (node (ref "U3") (pin "41") (pinfunction "NC_41") (pintype "passive"))
    )
    (net (code "59") (name "unconnected-(U3-NC-Pad57)") (class "Default")
      (node (ref "U3") (pin "57") (pinfunction "NC_57") (pintype "passive"))
    )
    (net (code "60") (name "unconnected-(U3-NC-Pad58)") (class "Default")
      (node (ref "U3") (pin "58") (pinfunction "NC_58") (pintype "passive"))
    )
    (net (code "61") (name "unconnected-(U3-NC-Pad59)") (class "Default")
      (node (ref "U3") (pin "59") (pinfunction "NC_59") (pintype "passive"))
    )
    (net (code "62") (name "unconnected-(U3-NC-Pad60)") (class "Default")
      (node (ref "U3") (pin "60") (pinfunction "NC_60") (pintype "passive"))
    )
    (net (code "63") (name "unconnected-(U3-NC-Pad61)") (class "Default")
      (node (ref "U3") (pin "61") (pinfunction "NC_61") (pintype "passive"))
    )
    (net (code "64") (name "unconnected-(U3-NC-Pad62)") (class "Default")
      (node (ref "U3") (pin "62") (pinfunction "NC_62") (pintype "passive"))
    )
    (net (code "65") (name "unconnected-(U3-P0_3-Pad74)") (class "Default")
      (node (ref "U3") (pin "74") (pinfunction "P0_3_74") (pintype "passive"))
    )
    (net (code "66") (name "unconnected-(U3-P0_5-Pad77)") (class "Default")
      (node (ref "U3") (pin "77") (pinfunction "P0_5_77") (pintype "passive"))
    )
    (net (code "67") (name "unconnected-(U3-P0_6-Pad78)") (class "Default")
      (node (ref "U3") (pin "78") (pinfunction "P0_6_78") (pintype "passive"))
    )
    (net (code "68") (name "unconnected-(U3-P0_7-Pad79)") (class "Default")
      (node (ref "U3") (pin "79") (pinfunction "P0_7_79") (pintype "passive"))
    )
    (net (code "69") (name "unconnected-(U3-P1_2-Pad22)") (class "Default")
      (node (ref "U3") (pin "22") (pinfunction "P1_2_22") (pintype "passive"))
    )
    (net (code "70") (name "unconnected-(U3-P1_3_TDO_SWV-Pad23)") (class "Default")
      (node (ref "U3") (pin "23") (pinfunction "P1_3_TDO_SWV_23") (pintype "passive"))
    )
    (net (code "71") (name "unconnected-(U3-P1_4_TDI-Pad24)") (class "Default")
      (node (ref "U3") (pin "24") (pinfunction "P1_4_TDI_24") (pintype "passive"))
    )
    (net (code "72") (name "unconnected-(U3-P1_5_NTRST-Pad25)") (class "Default")
      (node (ref "U3") (pin "25") (pinfunction "P1_5_NTRST_25") (pintype "passive"))
    )
    (net (code "73") (name "unconnected-(U3-P1_6-Pad27)") (class "Default")
      (node (ref "U3") (pin "27") (pinfunction "P1_6_27") (pintype "passive"))
    )
    (net (code "74") (name "unconnected-(U3-P1_7-Pad28)") (class "Default")
      (node (ref "U3") (pin "28") (pinfunction "P1_7_28") (pintype "passive"))
    )
    (net (code "75") (name "unconnected-(U3-P2_0-Pad95)") (class "Default")
      (node (ref "U3") (pin "95") (pinfunction "P2_0_95") (pintype "passive"))
    )
    (net (code "76") (name "unconnected-(U3-P2_1-Pad96)") (class "Default")
      (node (ref "U3") (pin "96") (pinfunction "P2_1_96") (pintype "passive"))
    )
    (net (code "77") (name "unconnected-(U3-P2_2-Pad97)") (class "Default")
      (node (ref "U3") (pin "97") (pinfunction "P2_2_97") (pintype "passive"))
    )
    (net (code "78") (name "unconnected-(U3-P2_3-Pad98)") (class "Default")
      (node (ref "U3") (pin "98") (pinfunction "P2_3_98") (pintype "passive"))
    )
    (net (code "79") (name "unconnected-(U3-P2_4-Pad99)") (class "Default")
      (node (ref "U3") (pin "99") (pinfunction "P2_4_99") (pintype "passive"))
    )
    (net (code "80") (name "unconnected-(U3-P2_5-Pad1)") (class "Default")
      (node (ref "U3") (pin "1") (pinfunction "P2_5_1") (pintype "passive"))
    )
    (net (code "81") (name "unconnected-(U3-P2_6-Pad2)") (class "Default")
      (node (ref "U3") (pin "2") (pinfunction "P2_6_2") (pintype "passive"))
    )
    (net (code "82") (name "unconnected-(U3-P2_7-Pad3)") (class "Default")
      (node (ref "U3") (pin "3") (pinfunction "P2_7_3") (pintype "passive"))
    )
    (net (code "83") (name "unconnected-(U3-P3_3-Pad47)") (class "Default")
      (node (ref "U3") (pin "47") (pinfunction "P3_3_47") (pintype "passive"))
    )
    (net (code "84") (name "unconnected-(U3-P3_4-Pad48)") (class "Default")
      (node (ref "U3") (pin "48") (pinfunction "P3_4_48") (pintype "passive"))
    )
    (net (code "85") (name "unconnected-(U3-P3_5-Pad49)") (class "Default")
      (node (ref "U3") (pin "49") (pinfunction "P3_5_49") (pintype "passive"))
    )
    (net (code "86") (name "unconnected-(U3-P3_7-Pad52)") (class "Default")
      (node (ref "U3") (pin "52") (pinfunction "P3_7_52") (pintype "passive"))
    )
    (net (code "87") (name "unconnected-(U3-P4_2-Pad80)") (class "Default")
      (node (ref "U3") (pin "80") (pinfunction "P4_2_80") (pintype "passive"))
    )
    (net (code "88") (name "unconnected-(U3-P4_3-Pad81)") (class "Default")
      (node (ref "U3") (pin "81") (pinfunction "P4_3_81") (pintype "passive"))
    )
    (net (code "89") (name "unconnected-(U3-P4_4-Pad82)") (class "Default")
      (node (ref "U3") (pin "82") (pinfunction "P4_4_82") (pintype "passive"))
    )
    (net (code "90") (name "unconnected-(U3-P4_5-Pad83)") (class "Default")
      (node (ref "U3") (pin "83") (pinfunction "P4_5_83") (pintype "passive"))
    )
    (net (code "91") (name "unconnected-(U3-P4_7-Pad85)") (class "Default")
      (node (ref "U3") (pin "85") (pinfunction "P4_7_85") (pintype "passive"))
    )
    (net (code "92") (name "unconnected-(U3-P5_0-Pad16)") (class "Default")
      (node (ref "U3") (pin "16") (pinfunction "P5_0_16") (pintype "passive"))
    )
    (net (code "93") (name "unconnected-(U3-P5_1-Pad17)") (class "Default")
      (node (ref "U3") (pin "17") (pinfunction "P5_1_17") (pintype "passive"))
    )
    (net (code "94") (name "unconnected-(U3-P5_2-Pad18)") (class "Default")
      (node (ref "U3") (pin "18") (pinfunction "P5_2_18") (pintype "passive"))
    )
    (net (code "95") (name "unconnected-(U3-P5_3-Pad19)") (class "Default")
      (node (ref "U3") (pin "19") (pinfunction "P5_3_19") (pintype "passive"))
    )
    (net (code "96") (name "unconnected-(U3-P5_4-Pad31)") (class "Default")
      (node (ref "U3") (pin "31") (pinfunction "P5_4_31") (pintype "passive"))
    )
    (net (code "97") (name "unconnected-(U3-P5_5-Pad32)") (class "Default")
      (node (ref "U3") (pin "32") (pinfunction "P5_5_32") (pintype "passive"))
    )
    (net (code "98") (name "unconnected-(U3-P5_6-Pad33)") (class "Default")
      (node (ref "U3") (pin "33") (pinfunction "P5_6_33") (pintype "passive"))
    )
    (net (code "99") (name "unconnected-(U3-P5_7-Pad34)") (class "Default")
      (node (ref "U3") (pin "34") (pinfunction "P5_7_34") (pintype "passive"))
    )
    (net (code "100") (name "unconnected-(U3-P6_0-Pad89)") (class "Default")
      (node (ref "U3") (pin "89") (pinfunction "P6_0_89") (pintype "passive"))
    )
    (net (code "101") (name "unconnected-(U3-P6_1-Pad90)") (class "Default")
      (node (ref "U3") (pin "90") (pinfunction "P6_1_90") (pintype "passive"))
    )
    (net (code "102") (name "unconnected-(U3-P6_2-Pad91)") (class "Default")
      (node (ref "U3") (pin "91") (pinfunction "P6_2_91") (pintype "passive"))
    )
    (net (code "103") (name "unconnected-(U3-P6_3-Pad92)") (class "Default")
      (node (ref "U3") (pin "92") (pinfunction "P6_3_92") (pintype "passive"))
    )
    (net (code "104") (name "unconnected-(U3-P6_4-Pad6)") (class "Default")
      (node (ref "U3") (pin "6") (pinfunction "P6_4_6") (pintype "passive"))
    )
    (net (code "105") (name "unconnected-(U3-P6_5-Pad7)") (class "Default")
      (node (ref "U3") (pin "7") (pinfunction "P6_5_7") (pintype "passive"))
    )
    (net (code "106") (name "unconnected-(U3-P6_6-Pad8)") (class "Default")
      (node (ref "U3") (pin "8") (pinfunction "P6_6_8") (pintype "passive"))
    )
    (net (code "107") (name "unconnected-(U3-P6_7-Pad9)") (class "Default")
      (node (ref "U3") (pin "9") (pinfunction "P6_7_9") (pintype "passive"))
    )
    (net (code "108") (name "unconnected-(U3-P12_0_I2C1_SCL-Pad53)") (class "Default")
      (node (ref "U3") (pin "53") (pinfunction "P12_0_I2C1_SCL_53") (pintype "passive"))
    )
    (net (code "109") (name "unconnected-(U3-P12_1_I2C1_SDA-Pad54)") (class "Default")
      (node (ref "U3") (pin "54") (pinfunction "P12_1_I2C1_SDA_54") (pintype "passive"))
    )
    (net (code "110") (name "unconnected-(U3-P12_2-Pad67)") (class "Default")
      (node (ref "U3") (pin "67") (pinfunction "P12_2_67") (pintype "passive"))
    )
    (net (code "111") (name "unconnected-(U3-P12_3-Pad68)") (class "Default")
      (node (ref "U3") (pin "68") (pinfunction "P12_3_68") (pintype "passive"))
    )
    (net (code "112") (name "unconnected-(U3-P12_6-Pad29)") (class "Default")
      (node (ref "U3") (pin "29") (pinfunction "P12_6_29") (pintype "passive"))
    )
    (net (code "113") (name "unconnected-(U3-P12_7-Pad30)") (class "Default")
      (node (ref "U3") (pin "30") (pinfunction "P12_7_30") (pintype "passive"))
    )
    (net (code "114") (name "unconnected-(U3-P15_0_MXTLO-Pad42)") (class "Default")
      (node (ref "U3") (pin "42") (pinfunction "P15_0_MXTLO_42") (pintype "passive"))
    )
    (net (code "115") (name "unconnected-(U3-P15_1_MXTLI-Pad43)") (class "Default")
      (node (ref "U3") (pin "43") (pinfunction "P15_1_MXTLI_43") (pintype "passive"))
    )
    (net (code "116") (name "unconnected-(U3-P15_2_KXTLO-Pad55)") (class "Default")
      (node (ref "U3") (pin "55") (pinfunction "P15_2_KXTLO_55") (pintype "passive"))
    )
    (net (code "117") (name "unconnected-(U3-P15_3_KXTLI-Pad56)") (class "Default")
      (node (ref "U3") (pin "56") (pinfunction "P15_3_KXTLI_56") (pintype "passive"))
    )
    (net (code "118") (name "unconnected-(U3-P15_4-Pad93)") (class "Default")
      (node (ref "U3") (pin "93") (pinfunction "P15_4_93") (pintype "passive"))
    )
    (net (code "119") (name "unconnected-(U3-P15_5-Pad94)") (class "Default")
      (node (ref "U3") (pin "94") (pinfunction "P15_5_94") (pintype "passive"))
    )
    (net (code "120") (name "unconnected-(U3-P15_6_DP-Pad35)") (class "Default")
      (node (ref "U3") (pin "35") (pinfunction "P15_6_DP_35") (pintype "passive"))
    )
    (net (code "121") (name "unconnected-(U3-P15_7_DM-Pad36)") (class "Default")
      (node (ref "U3") (pin "36") (pinfunction "P15_7_DM_36") (pintype "passive"))
    )
    (net (code "122") (name "unconnected-(U3-VSSD-Pad66)") (class "Default")
      (node (ref "U3") (pin "66") (pinfunction "VSSD_66") (pintype "passive"))
    )
    (net (code "123") (name "unconnected-(U4-AD0{slash}DIO0-Pad20)") (class "Default")
      (node (ref "U4") (pin "20") (pinfunction "AD0/DIO0_20") (pintype "bidirectional"))
    )
    (net (code "124") (name "unconnected-(U4-AD1{slash}DIO1-Pad19)") (class "Default")
      (node (ref "U4") (pin "19") (pinfunction "AD1/DIO1_19") (pintype "bidirectional"))
    )
    (net (code "125") (name "unconnected-(U4-AD2{slash}DIO2-Pad18)") (class "Default")
      (node (ref "U4") (pin "18") (pinfunction "AD2/DIO2_18") (pintype "bidirectional"))
    )
    (net (code "126") (name "unconnected-(U4-AD3{slash}DIO3-Pad17)") (class "Default")
      (node (ref "U4") (pin "17") (pinfunction "AD3/DIO3_17") (pintype "bidirectional"))
    )
    (net (code "127") (name "unconnected-(U4-AD4{slash}DIO4-Pad11)") (class "Default")
      (node (ref "U4") (pin "11") (pinfunction "AD4/DIO4_11") (pintype "bidirectional"))
    )
    (net (code "128") (name "unconnected-(U4-ASC{slash}AD5{slash}DIO5-Pad15)") (class "Default")
      (node (ref "U4") (pin "15") (pinfunction "ASC/AD5/DIO5_15") (pintype "bidirectional"))
    )
    (net (code "129") (name "unconnected-(U4-CTS{slash}DIO7-Pad12)") (class "Default")
      (node (ref "U4") (pin "12") (pinfunction "CTS/DIO7_12") (pintype "bidirectional"))
    )
    (net (code "130") (name "unconnected-(U4-DO8-Pad4)") (class "Default")
      (node (ref "U4") (pin "4") (pinfunction "DO8_4") (pintype "output"))
    )
    (net (code "131") (name "unconnected-(U4-ON{slash}SLEEP-Pad13)") (class "Default")
      (node (ref "U4") (pin "13") (pinfunction "ON/SLEEP_13") (pintype "output"))
    )
    (net (code "132") (name "unconnected-(U4-PWM0{slash}RSSI-Pad6)") (class "Default")
      (node (ref "U4") (pin "6") (pinfunction "PWM0/RSSI_6") (pintype "output"))
    )
    (net (code "133") (name "unconnected-(U4-PWM1-Pad7)") (class "Default")
      (node (ref "U4") (pin "7") (pinfunction "PWM1_7") (pintype "output"))
    )
    (net (code "134") (name "unconnected-(U4-RESERVED-Pad8)") (class "Default")
      (node (ref "U4") (pin "8") (pinfunction "RESERVED_8") (pintype "no_connect"))
    )
    (net (code "135") (name "unconnected-(U4-RESET-Pad5)") (class "Default")
      (node (ref "U4") (pin "5") (pinfunction "RESET_5") (pintype "input"))
    )
    (net (code "136") (name "unconnected-(U4-RTS{slash}AD6{slash}DIO6-Pad16)") (class "Default")
      (node (ref "U4") (pin "16") (pinfunction "RTS/AD6/DIO6_16") (pintype "bidirectional"))
    )
    (net (code "137") (name "unconnected-(U4-VREF-Pad14)") (class "Default")
      (node (ref "U4") (pin "14") (pinfunction "VREF_14") (pintype "input"))
    )
  )
)
